# V4_0.net
KiCad netlist of a schematic drawn in Altium Designer
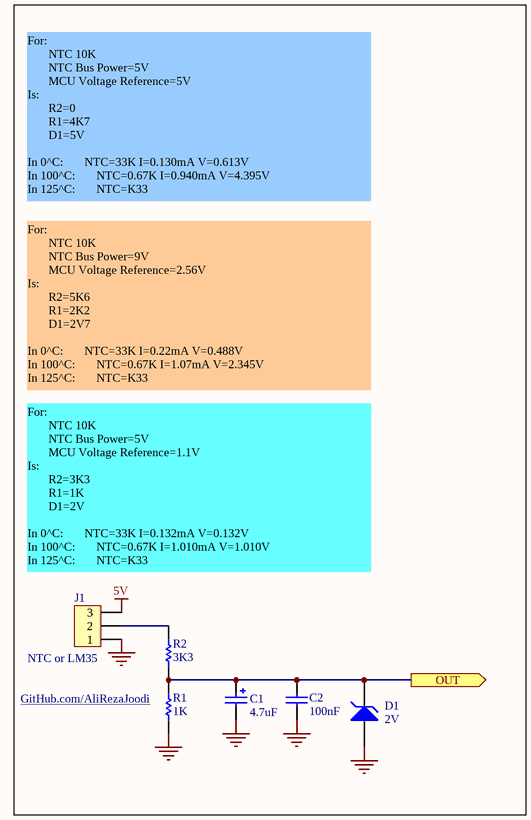
[diagram p0: V4.0.SchDoc]

(export (version "E")
  (design (tool "Eeschema 10.0.6"))
  (components
    (comp (ref "C1")
      (value "4.7uF")
      (footprint "CAPPR2.5-6.3x5")
      (description "Polarized Capacitor (Radial)")
      (fields (field (name "MANUFACTURER") "Generic Components") (field (name "PUBLISHER") "Altium Limited"))
      (libsource (lib "Miscellaneous Devices") (part "Cap Pol1"))
    )
    (comp (ref "C2")
      (value "100nF")
      (footprint "CAPNTO2.54-3.05x1.78A")
      (description "Capacitor")
      (fields (field (name "MANUFACTURER") "Generic Components") (field (name "PUBLISHER") "Altium Limited"))
      (libsource (lib "Miscellaneous Devices") (part "Cap"))
    )
    (comp (ref "D1")
      (value "2V")
      (footprint "DIODE0.4_Glass")
      (description "Zener Diode")
      (fields (field (name "MANUFACTURER") "Generic Components") (field (name "PUBLISHER") "Altium Limited"))
      (libsource (lib "Miscellaneous Devices") (part "D Zener"))
    )
    (comp (ref "J1")
      (value "3PIN")
      (description "Connector, Header, 3Pin")
      (libsource (lib "Connector") (part "Connector_Header_3Pin"))
    )
    (comp (ref "R1")
      (value "1K")
      (footprint "AXIAL-0.4")
      (description "Resistor")
      (fields (field (name "PUBLISHER") "Altium Limited"))
      (libsource (lib "Miscellaneous Devices") (part "Res1"))
    )
    (comp (ref "R2")
      (value "3K3")
      (footprint "AXIAL-0.4")
      (description "Resistor")
      (fields (field (name "PUBLISHER") "Altium Limited"))
      (libsource (lib "Miscellaneous Devices") (part "Res1"))
    )
  )
  (nets
    (net (code "1") (name "/OUT") (class "Default")
      (node (ref "C1") (pin "1") (pinfunction "1_1") (pintype "passive"))
      (node (ref "C2") (pin "2") (pinfunction "2_2") (pintype "passive"))
      (node (ref "D1") (pin "2") (pinfunction "K_2") (pintype "passive"))
      (node (ref "R1") (pin "1") (pinfunction "1_1") (pintype "passive"))
      (node (ref "R2") (pin "2") (pinfunction "2_2") (pintype "passive"))
    )
    (net (code "2") (name "5V") (class "Default")
      (node (ref "J1") (pin "3") (pinfunction "3_3") (pintype "passive"))
    )
    (net (code "3") (name "GND") (class "Default")
      (node (ref "C1") (pin "2") (pinfunction "2_2") (pintype "passive"))
      (node (ref "C2") (pin "1") (pinfunction "1_1") (pintype "passive"))
      (node (ref "D1") (pin "1") (pinfunction "A_1") (pintype "passive"))
      (node (ref "J1") (pin "1") (pinfunction "1_1") (pintype "passive"))
      (node (ref "R1") (pin "2") (pinfunction "2_2") (pintype "passive"))
    )
    (net (code "4") (name "Net-(J1-Pad2)") (class "Default")
      (node (ref "J1") (pin "2") (pinfunction "2_2") (pintype "passive"))
      (node (ref "R2") (pin "1") (pinfunction "1_1") (pintype "passive"))
    )
  )
)
